# bodo09.net
KiCad netlist of a schematic drawn in EAGLE
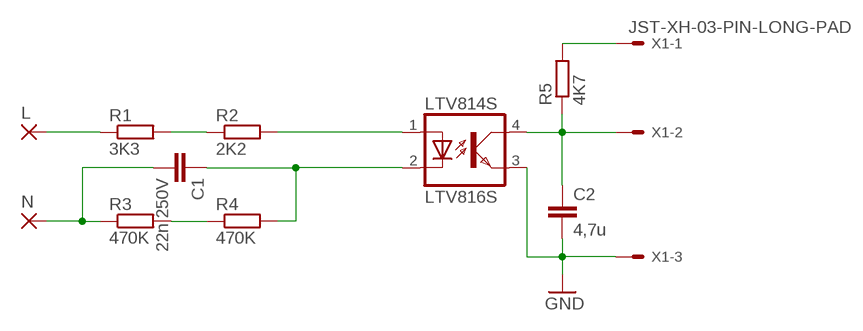
[diagram p0: schematic, sheet 1]

(export (version "E")
  (design (tool "Eeschema 10.0.6"))
  (components
    (comp (ref "C1")
      (value "22n 250V")
      (footprint "eagle-import:C2220K")
      (libsource (lib "eagle-import") (part "C-EUC2220K"))
    )
    (comp (ref "C2")
      (value "4,7u")
      (footprint "eagle-import:C1206K")
      (libsource (lib "eagle-import") (part "C-EUC1206K"))
    )
    (comp (ref "L")
      (value "3,81/1,4")
      (footprint "eagle-import:3,81_1,4")
      (libsource (lib "eagle-import") (part "3,81/1,4"))
    )
    (comp (ref "LTV814S")
      (value "LTV816S")
      (footprint "eagle-import:SMD4")
      (libsource (lib "eagle-import") (part "LTV816S"))
    )
    (comp (ref "N")
      (value "3,81/1,4")
      (footprint "eagle-import:3,81_1,4")
      (libsource (lib "eagle-import") (part "3,81/1,4"))
    )
    (comp (ref "R1")
      (value "3K3")
      (footprint "eagle-import:R1206")
      (libsource (lib "eagle-import") (part "R-EU_R1206"))
    )
    (comp (ref "R2")
      (value "2K2")
      (footprint "eagle-import:R1206")
      (libsource (lib "eagle-import") (part "R-EU_R1206"))
    )
    (comp (ref "R3")
      (value "470K")
      (footprint "eagle-import:R1206")
      (libsource (lib "eagle-import") (part "R-EU_R1206"))
    )
    (comp (ref "R4")
      (value "470K")
      (footprint "eagle-import:R1206")
      (libsource (lib "eagle-import") (part "R-EU_R1206"))
    )
    (comp (ref "R5")
      (value "4K7")
      (footprint "eagle-import:R0805")
      (libsource (lib "eagle-import") (part "R-EU_R0805"))
    )
    (comp (ref "X1")
      (value "JST-XH-03-PIN-LONG-PAD")
      (footprint "eagle-import:JST-XH-03-PACKAGE-LONG-PAD")
      (libsource (lib "eagle-import") (part "JST-XH-03-PIN-LONG-PAD"))
    )
  )
  (nets
    (net (code "1") (name "GND") (class "Default")
      (node (ref "C2") (pin "2") (pinfunction "2_2") (pintype "passive"))
      (node (ref "LTV814S") (pin "3") (pinfunction "EMIT_3") (pintype "passive"))
      (node (ref "X1") (pin "3") (pinfunction "S_3") (pintype "passive"))
    )
    (net (code "2") (name "Net-(L-P)") (class "Default")
      (node (ref "L") (pin "1") (pinfunction "P_1") (pintype "passive"))
      (node (ref "R1") (pin "1") (pinfunction "1_1") (pintype "passive"))
    )
    (net (code "3") (name "Net-(LTV814S-A)") (class "Default")
      (node (ref "LTV814S") (pin "1") (pinfunction "A_1") (pintype "passive"))
      (node (ref "R2") (pin "2") (pinfunction "2_2") (pintype "passive"))
    )
    (net (code "4") (name "Net-(LTV814S-C)") (class "Default")
      (node (ref "C1") (pin "1") (pinfunction "1_1") (pintype "passive"))
      (node (ref "LTV814S") (pin "2") (pinfunction "C_2") (pintype "passive"))
      (node (ref "R4") (pin "2") (pinfunction "2_2") (pintype "passive"))
    )
    (net (code "5") (name "Net-(LTV814S-COL)") (class "Default")
      (node (ref "C2") (pin "1") (pinfunction "1_1") (pintype "passive"))
      (node (ref "LTV814S") (pin "4") (pinfunction "COL_4") (pintype "passive"))
      (node (ref "R5") (pin "1") (pinfunction "1_1") (pintype "passive"))
      (node (ref "X1") (pin "2") (pinfunction "S_2") (pintype "passive"))
    )
    (net (code "6") (name "Net-(N-P)") (class "Default")
      (node (ref "C1") (pin "2") (pinfunction "2_2") (pintype "passive"))
      (node (ref "N") (pin "1") (pinfunction "P_1") (pintype "passive"))
      (node (ref "R3") (pin "1") (pinfunction "1_1") (pintype "passive"))
    )
    (net (code "7") (name "Net-(R1-Pad2)") (class "Default")
      (node (ref "R1") (pin "2") (pinfunction "2_2") (pintype "passive"))
      (node (ref "R2") (pin "1") (pinfunction "1_1") (pintype "passive"))
    )
    (net (code "8") (name "Net-(R3-Pad2)") (class "Default")
      (node (ref "R3") (pin "2") (pinfunction "2_2") (pintype "passive"))
      (node (ref "R4") (pin "1") (pinfunction "1_1") (pintype "passive"))
    )
    (net (code "9") (name "Net-(X1A-S)") (class "Default")
      (node (ref "R5") (pin "2") (pinfunction "2_2") (pintype "passive"))
      (node (ref "X1") (pin "1") (pinfunction "S_1") (pintype "passive"))
    )
  )
)
